# Mother_Board_USB.net
KiCad netlist of a schematic drawn in Altium Designer
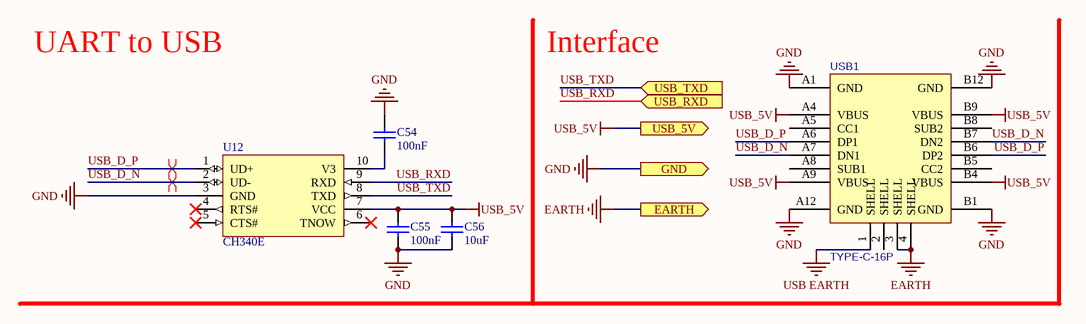
[diagram p0: Mother Board USB.SchDoc]

(export (version "E")
  (design (tool "Eeschema 10.0.6"))
  (components
    (comp (ref "C54") (value "100nF") (footprint "C0603") (libsource (lib "Cap") (part "Cap_100nF")))
    (comp (ref "C55") (value "100nF") (footprint "C0603") (libsource (lib "Cap") (part "Cap_100nF")))
    (comp (ref "C56") (value "10uF") (footprint "C0603") (libsource (lib "Cap") (part "Cap")))
    (comp (ref "U12")
      (value "CH340E")
      (footprint "MSOP10")
      (description "USB to TTL Serial / UART")
      (libsource (lib "All lib") (part "CH340E"))
    )
    (comp (ref "USB1")
      (value "TYPE-C-16P")
      (footprint "USB-C_16P")
      (fields
        (field (name "BOM_SUPPLIER PART") "C709357")
        (field (name "BOM_MANUFACTURER PART") "KH-TYPE-C-16P")
        (field (name "CONTRIBUTOR") "LCSC")
      )
      (libsource (lib "All lib") (part "USB-C-16P"))
    )
  )
  (nets
    (net (code "1") (name "/USB_D_N") (class "Default")
      (node (ref "U12") (pin "2") (pinfunction "UD-_2") (pintype "bidirectional"))
      (node (ref "USB1") (pin "A7") (pinfunction "DN1_A7") (pintype "passive"))
      (node (ref "USB1") (pin "B7") (pinfunction "DN2_B7") (pintype "passive"))
    )
    (net (code "2") (name "/USB_D_P") (class "Default")
      (node (ref "U12") (pin "1") (pinfunction "UD+_1") (pintype "bidirectional"))
      (node (ref "USB1") (pin "A6") (pinfunction "DP1_A6") (pintype "passive"))
      (node (ref "USB1") (pin "B6") (pinfunction "DP2_B6") (pintype "passive"))
    )
    (net (code "3") (name "/USB_RXD") (class "Default")
      (node (ref "U12") (pin "9") (pinfunction "RXD_9") (pintype "input"))
    )
    (net (code "4") (name "/USB_TXD") (class "Default")
      (node (ref "U12") (pin "8") (pinfunction "TXD_8") (pintype "output"))
    )
    (net (code "5") (name "EARTH") (class "Default")
      (node (ref "USB1") (pin "3") (pinfunction "SHELL_3") (pintype "passive"))
      (node (ref "USB1") (pin "4") (pinfunction "SHELL_4") (pintype "passive"))
    )
    (net (code "6") (name "GND") (class "Default")
      (node (ref "C54") (pin "2") (pinfunction "2_2") (pintype "passive"))
      (node (ref "C55") (pin "2") (pinfunction "2_2") (pintype "passive"))
      (node (ref "C56") (pin "2") (pinfunction "2_2") (pintype "passive"))
      (node (ref "U12") (pin "3") (pinfunction "GND_3") (pintype "power_in"))
      (node (ref "USB1") (pin "A1") (pinfunction "GND_A1") (pintype "passive"))
      (node (ref "USB1") (pin "A12") (pinfunction "GND_A12") (pintype "passive"))
      (node (ref "USB1") (pin "B1") (pinfunction "GND_B1") (pintype "passive"))
      (node (ref "USB1") (pin "B12") (pinfunction "GND_B12") (pintype "passive"))
    )
    (net (code "7") (name "Net-(U12-V3)") (class "Default")
      (node (ref "C54") (pin "1") (pinfunction "1_1") (pintype "passive"))
      (node (ref "U12") (pin "10") (pinfunction "V3_10") (pintype "power_in"))
    )
    (net (code "8") (name "USB EARTH") (class "Default")
      (node (ref "USB1") (pin "1") (pinfunction "SHELL_1") (pintype "passive"))
    )
    (net (code "9") (name "USB_5V") (class "Default")
      (node (ref "C55") (pin "1") (pinfunction "1_1") (pintype "passive"))
      (node (ref "C56") (pin "1") (pinfunction "1_1") (pintype "passive"))
      (node (ref "U12") (pin "7") (pinfunction "VCC_7") (pintype "power_in"))
      (node (ref "USB1") (pin "A4") (pinfunction "VBUS_A4") (pintype "passive"))
      (node (ref "USB1") (pin "A9") (pinfunction "VBUS_A9") (pintype "passive"))
      (node (ref "USB1") (pin "B4") (pinfunction "VBUS_B4") (pintype "passive"))
      (node (ref "USB1") (pin "B9") (pinfunction "VBUS_B9") (pintype "passive"))
    )
    (net (code "10") (name "unconnected-(U12-CTS#-Pad5)") (class "Default")
      (node (ref "U12") (pin "5") (pinfunction "CTS#_5") (pintype "input+no_connect"))
    )
    (net (code "11") (name "unconnected-(U12-RTS#-Pad4)") (class "Default")
      (node (ref "U12") (pin "4") (pinfunction "RTS#_4") (pintype "output+no_connect"))
    )
    (net (code "12") (name "unconnected-(U12-TNOW-Pad6)") (class "Default")
      (node (ref "U12") (pin "6") (pinfunction "TNOW_6") (pintype "output+no_connect"))
    )
    (net (code "13") (name "unconnected-(USB1-CC1-PadA5)") (class "Default")
      (node (ref "USB1") (pin "A5") (pinfunction "CC1_A5") (pintype "passive"))
    )
    (net (code "14") (name "unconnected-(USB1-CC2-PadB5)") (class "Default")
      (node (ref "USB1") (pin "B5") (pinfunction "CC2_B5") (pintype "passive"))
    )
    (net (code "15") (name "unconnected-(USB1-SHELL-Pad2)") (class "Default")
      (node (ref "USB1") (pin "2") (pinfunction "SHELL_2") (pintype "passive"))
    )
    (net (code "16") (name "unconnected-(USB1-SUB1-PadA8)") (class "Default")
      (node (ref "USB1") (pin "A8") (pinfunction "SUB1_A8") (pintype "passive"))
    )
    (net (code "17") (name "unconnected-(USB1-SUB2-PadB8)") (class "Default")
      (node (ref "USB1") (pin "B8") (pinfunction "SUB2_B8") (pintype "passive"))
    )
  )
)
